# master_jorge3newIMU.net
KiCad netlist of a schematic drawn in EAGLE
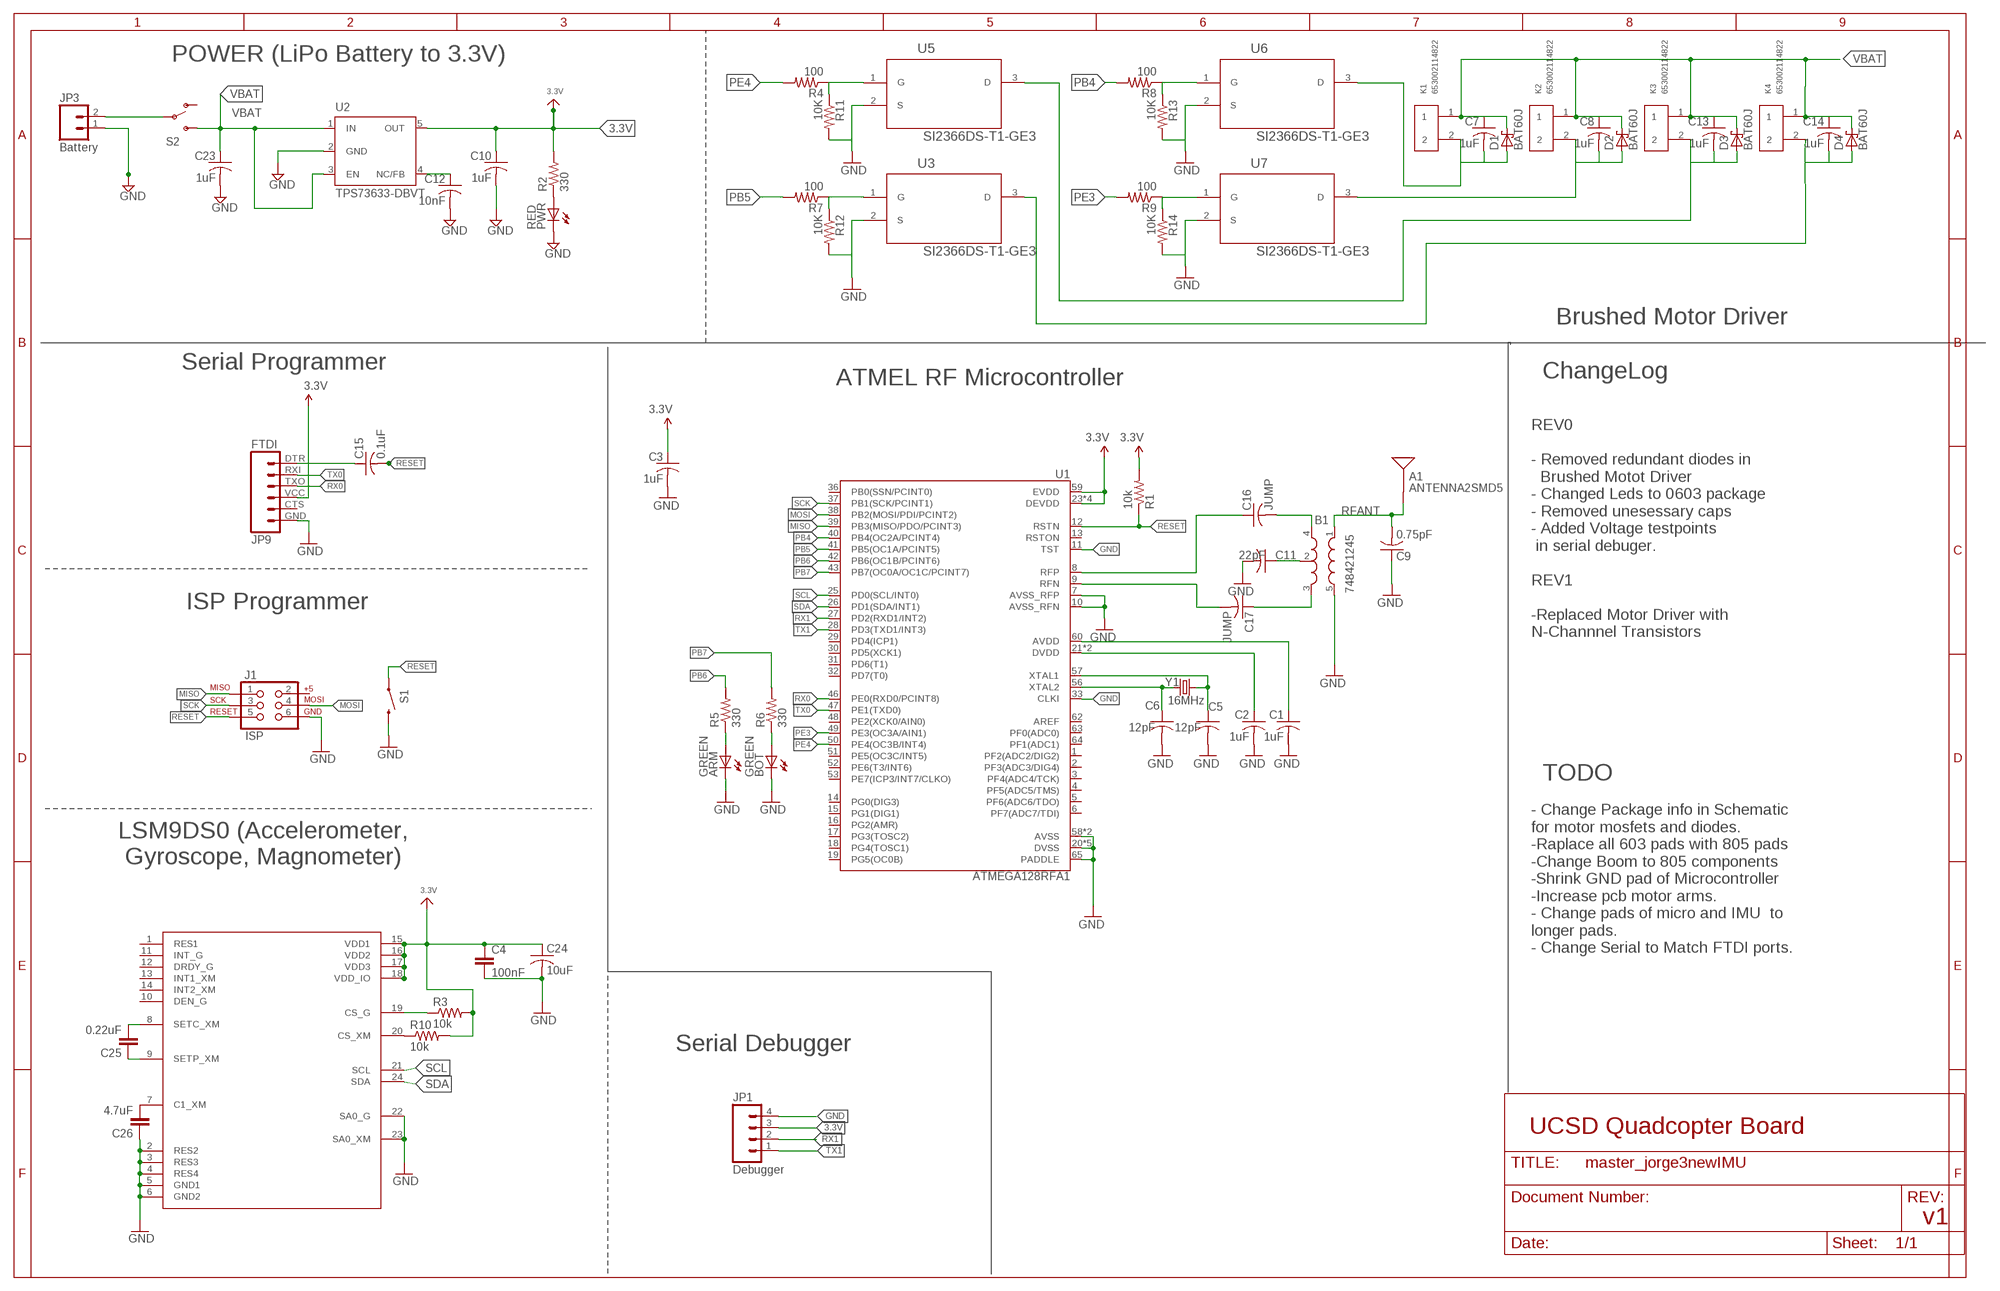
[diagram p0: schematic, sheet 1]

(export (version "E")
  (design (tool "Eeschema 10.0.6"))
  (components
    (comp (ref "A1")
      (value "ANTENNA2SMD5")
      (footprint "eagle-import:ANTENNA-CHIP5")
      (libsource (lib "eagle-import") (part "ANTENNA2SMD5"))
    )
    (comp (ref "ARM")
      (value "GREEN")
      (footprint "eagle-import:CHIP-LED0805")
      (libsource (lib "eagle-import") (part "LEDCHIP-LED0805"))
    )
    (comp (ref "B1")
      (value "748421245")
      (footprint "eagle-import:BALUN")
      (libsource (lib "eagle-import") (part "BALUN0805"))
    )
    (comp (ref "BOT")
      (value "GREEN")
      (footprint "eagle-import:CHIP-LED0805")
      (libsource (lib "eagle-import") (part "LEDCHIP-LED0805"))
    )
    (comp (ref "C1")
      (value "1uF")
      (footprint "eagle-import:C0805")
      (libsource (lib "eagle-import") (part "resistor_C-USC0805"))
    )
    (comp (ref "C2")
      (value "1uF")
      (footprint "eagle-import:C0805")
      (libsource (lib "eagle-import") (part "resistor_C-USC0805"))
    )
    (comp (ref "C3")
      (value "1uF")
      (footprint "eagle-import:C0805")
      (libsource (lib "eagle-import") (part "resistor_C-USC0805"))
    )
    (comp (ref "C4")
      (value "100nF")
      (footprint "eagle-import:0805")
      (libsource (lib "eagle-import") (part "CAP0805"))
    )
    (comp (ref "C5")
      (value "12pF")
      (footprint "eagle-import:C0805")
      (libsource (lib "eagle-import") (part "resistor_C-USC0805"))
    )
    (comp (ref "C6")
      (value "12pF")
      (footprint "eagle-import:C0805")
      (libsource (lib "eagle-import") (part "resistor_C-USC0805"))
    )
    (comp (ref "C7")
      (value "1uF")
      (footprint "eagle-import:C0805")
      (libsource (lib "eagle-import") (part "resistor_C-USC0805"))
    )
    (comp (ref "C8")
      (value "1uF")
      (footprint "eagle-import:C0805")
      (libsource (lib "eagle-import") (part "resistor_C-USC0805"))
    )
    (comp (ref "C9")
      (value "0.75pF")
      (footprint "eagle-import:C0805")
      (libsource (lib "eagle-import") (part "resistor_C-USC0805"))
    )
    (comp (ref "C10")
      (value "1uF")
      (footprint "eagle-import:C0805")
      (libsource (lib "eagle-import") (part "resistor_C-USC0805"))
    )
    (comp (ref "C11")
      (value "22pF")
      (footprint "eagle-import:C0805")
      (libsource (lib "eagle-import") (part "resistor_C-USC0805"))
    )
    (comp (ref "C12")
      (value "10nF")
      (footprint "eagle-import:C0805")
      (libsource (lib "eagle-import") (part "resistor_C-USC0805"))
    )
    (comp (ref "C13")
      (value "1uF")
      (footprint "eagle-import:C0805")
      (libsource (lib "eagle-import") (part "resistor_C-USC0805"))
    )
    (comp (ref "C14")
      (value "1uF")
      (footprint "eagle-import:C0805")
      (libsource (lib "eagle-import") (part "resistor_C-USC0805"))
    )
    (comp (ref "C15")
      (value "0.1uF")
      (footprint "eagle-import:C0805")
      (libsource (lib "eagle-import") (part "resistor_C-USC0805"))
    )
    (comp (ref "C16")
      (value "JUMP")
      (footprint "eagle-import:C0805")
      (libsource (lib "eagle-import") (part "resistor_C-USC0805"))
    )
    (comp (ref "C17")
      (value "JUMP")
      (footprint "eagle-import:C0805")
      (libsource (lib "eagle-import") (part "resistor_C-USC0805"))
    )
    (comp (ref "C23")
      (value "1uF")
      (footprint "eagle-import:C0805")
      (libsource (lib "eagle-import") (part "resistor_C-USC0805"))
    )
    (comp (ref "C24")
      (value "10uF")
      (footprint "eagle-import:C0805")
      (libsource (lib "eagle-import") (part "C-USC0805"))
    )
    (comp (ref "C25")
      (value "0.22uF")
      (footprint "eagle-import:0805")
      (libsource (lib "eagle-import") (part "CAP0805"))
    )
    (comp (ref "C26")
      (value "4.7uF")
      (footprint "eagle-import:0805")
      (libsource (lib "eagle-import") (part "CAP0805"))
    )
    (comp (ref "D1")
      (value "BAT60J")
      (footprint "eagle-import:SOD323_ST")
      (libsource (lib "eagle-import") (part "BAT60J"))
    )
    (comp (ref "D2")
      (value "BAT60J")
      (footprint "eagle-import:SOD323_ST")
      (libsource (lib "eagle-import") (part "BAT60J"))
    )
    (comp (ref "D3")
      (value "BAT60J")
      (footprint "eagle-import:SOD323_ST")
      (libsource (lib "eagle-import") (part "BAT60J"))
    )
    (comp (ref "D4")
      (value "BAT60J")
      (footprint "eagle-import:SOD323_ST")
      (libsource (lib "eagle-import") (part "BAT60J"))
    )
    (comp (ref "J1")
      (value "ISP")
      (footprint "eagle-import:2X3-NS")
      (libsource (lib "eagle-import") (part "AVR_SPI_PRG_6NS"))
    )
    (comp (ref "JP1")
      (value "Debugger")
      (footprint "eagle-import:1X04")
      (libsource (lib "eagle-import") (part "M04PTH"))
    )
    (comp (ref "JP3")
      (value "Battery")
      (footprint "eagle-import:1X02")
      (libsource (lib "eagle-import") (part "M02PTH"))
    )
    (comp (ref "JP9")
      (value "FTDI")
      (footprint "eagle-import:FTDI_BASIC")
      (libsource (lib "eagle-import") (part "FTDI_BASICPTH"))
    )
    (comp (ref "K1")
      (value "653002114822")
      (footprint "eagle-import:653002114822")
      (libsource (lib "eagle-import") (part "653002114822"))
    )
    (comp (ref "K2")
      (value "653002114822")
      (footprint "eagle-import:653002114822")
      (libsource (lib "eagle-import") (part "653002114822"))
    )
    (comp (ref "K3")
      (value "653002114822")
      (footprint "eagle-import:653002114822")
      (libsource (lib "eagle-import") (part "653002114822"))
    )
    (comp (ref "K4")
      (value "653002114822")
      (footprint "eagle-import:653002114822")
      (libsource (lib "eagle-import") (part "653002114822"))
    )
    (comp (ref "PWR")
      (value "RED")
      (footprint "eagle-import:CHIP-LED0805")
      (libsource (lib "eagle-import") (part "LEDCHIP-LED0805"))
    )
    (comp (ref "R1")
      (value "10k")
      (footprint "eagle-import:R0805")
      (libsource (lib "eagle-import") (part "R-US_R0805"))
    )
    (comp (ref "R2")
      (value "330")
      (footprint "eagle-import:R0805")
      (libsource (lib "eagle-import") (part "R-US_R0805"))
    )
    (comp (ref "R3")
      (value "10k")
      (footprint "eagle-import:0805")
      (libsource (lib "eagle-import") (part "RESISTOR0805-RES"))
    )
    (comp (ref "R4")
      (value "100")
      (footprint "eagle-import:R0805")
      (libsource (lib "eagle-import") (part "R-US_R0805"))
    )
    (comp (ref "R5")
      (value "330")
      (footprint "eagle-import:R0805")
      (libsource (lib "eagle-import") (part "R-US_R0805"))
    )
    (comp (ref "R6")
      (value "330")
      (footprint "eagle-import:R0805")
      (libsource (lib "eagle-import") (part "R-US_R0805"))
    )
    (comp (ref "R7")
      (value "100")
      (footprint "eagle-import:R0805")
      (libsource (lib "eagle-import") (part "R-US_R0805"))
    )
    (comp (ref "R8")
      (value "100")
      (footprint "eagle-import:R0805")
      (libsource (lib "eagle-import") (part "R-US_R0805"))
    )
    (comp (ref "R9")
      (value "100")
      (footprint "eagle-import:R0805")
      (libsource (lib "eagle-import") (part "R-US_R0805"))
    )
    (comp (ref "R10")
      (value "10k")
      (footprint "eagle-import:0805")
      (libsource (lib "eagle-import") (part "RESISTOR0805-RES"))
    )
    (comp (ref "R11")
      (value "10K")
      (footprint "eagle-import:R0805")
      (libsource (lib "eagle-import") (part "R-US_R0805"))
    )
    (comp (ref "R12")
      (value "10K")
      (footprint "eagle-import:R0805")
      (libsource (lib "eagle-import") (part "R-US_R0805"))
    )
    (comp (ref "R13")
      (value "10K")
      (footprint "eagle-import:R0805")
      (libsource (lib "eagle-import") (part "R-US_R0805"))
    )
    (comp (ref "R14")
      (value "10K")
      (footprint "eagle-import:R0805")
      (libsource (lib "eagle-import") (part "R-US_R0805"))
    )
    (comp (ref "S1")
      (value "SWITCH-MOMENTARY-2SMD")
      (footprint "eagle-import:TACTILE_SWITCH_SMD")
      (libsource (lib "eagle-import") (part "SWITCH-MOMENTARY-2SMD"))
    )
    (comp (ref "S2")
      (value "SWITCH-SPDTPTH")
      (footprint "eagle-import:SWITCH-SPDT")
      (libsource (lib "eagle-import") (part "SWITCH-SPDTPTH"))
    )
    (comp (ref "U1")
      (value "ATMEGA128RFA1")
      (footprint "eagle-import:QFN-64")
      (libsource (lib "eagle-import") (part "ATMEGA128RFA1"))
    )
    (comp (ref "U2")
      (value "TPS73633-DBVT")
      (footprint "eagle-import:SOT23-DBV")
      (libsource (lib "eagle-import") (part "TPS73633-DBVT"))
    )
    (comp (ref "U3")
      (value "SI2366DS-T1-GE3")
      (footprint "eagle-import:SOT95P237X112-3N")
      (libsource (lib "eagle-import") (part "SI2366DS-T1-GE3"))
    )
    (comp (ref "U4")
      (value "LSM9DS0")
      (footprint "eagle-import:LGA-24")
      (libsource (lib "eagle-import") (part "LSM9DS0"))
    )
    (comp (ref "U5")
      (value "SI2366DS-T1-GE3")
      (footprint "eagle-import:SOT95P237X112-3N")
      (libsource (lib "eagle-import") (part "SI2366DS-T1-GE3"))
    )
    (comp (ref "U6")
      (value "SI2366DS-T1-GE3")
      (footprint "eagle-import:SOT95P237X112-3N")
      (libsource (lib "eagle-import") (part "SI2366DS-T1-GE3"))
    )
    (comp (ref "U7")
      (value "SI2366DS-T1-GE3")
      (footprint "eagle-import:SOT95P237X112-3N")
      (libsource (lib "eagle-import") (part "SI2366DS-T1-GE3"))
    )
    (comp (ref "Y1")
      (value "16MHz")
      (footprint "eagle-import:CRYSTAL-SMD-5X3")
      (libsource (lib "eagle-import") (part "CRYSTAL5X3"))
    )
  )
  (nets
    (net (code "1") (name "/RFANT") (class "Default")
      (node (ref "A1") (pin "FEED") (pinfunction "SIGNAL_FEED") (pintype "bidirectional"))
      (node (ref "B1") (pin "1") (pinfunction "IN_1") (pintype "bidirectional"))
      (node (ref "C9") (pin "2") (pinfunction "2_2") (pintype "passive"))
    )
    (net (code "2") (name "3.3V") (class "Default")
      (node (ref "C10") (pin "1") (pinfunction "1_1") (pintype "passive"))
      (node (ref "C24") (pin "1") (pinfunction "1_1") (pintype "passive"))
      (node (ref "C3") (pin "1") (pinfunction "1_1") (pintype "passive"))
      (node (ref "C4") (pin "1") (pinfunction "1_1") (pintype "passive"))
      (node (ref "JP1") (pin "3") (pinfunction "3_3") (pintype "passive"))
      (node (ref "JP9") (pin "VCC") (pinfunction "4_VCC") (pintype "passive"))
      (node (ref "R1") (pin "2") (pinfunction "2_2") (pintype "passive"))
      (node (ref "R10") (pin "2") (pinfunction "2_2") (pintype "passive"))
      (node (ref "R2") (pin "2") (pinfunction "2_2") (pintype "passive"))
      (node (ref "R3") (pin "2") (pinfunction "2_2") (pintype "passive"))
      (node (ref "U1") (pin "23") (pinfunction "DEVDD_23") (pintype "bidirectional"))
      (node (ref "U1") (pin "34") (pinfunction "DEVDD_34") (pintype "bidirectional"))
      (node (ref "U1") (pin "44") (pinfunction "DEVDD_44") (pintype "bidirectional"))
      (node (ref "U1") (pin "54") (pinfunction "DEVDD_54") (pintype "bidirectional"))
      (node (ref "U1") (pin "59") (pinfunction "EVDD_59") (pintype "bidirectional"))
      (node (ref "U2") (pin "5") (pinfunction "OUT_5") (pintype "passive"))
      (node (ref "U4") (pin "15") (pinfunction "VDD1_15") (pintype "bidirectional"))
      (node (ref "U4") (pin "16") (pinfunction "VDD2_16") (pintype "bidirectional"))
      (node (ref "U4") (pin "17") (pinfunction "VDD3_17") (pintype "bidirectional"))
      (node (ref "U4") (pin "18") (pinfunction "VDD_IO_18") (pintype "bidirectional"))
    )
    (net (code "3") (name "GND") (class "Default")
      (node (ref "ARM") (pin "C") (pinfunction "C_C") (pintype "passive"))
      (node (ref "B1") (pin "5") (pinfunction "GND_5") (pintype "bidirectional"))
      (node (ref "BOT") (pin "C") (pinfunction "C_C") (pintype "passive"))
      (node (ref "C1") (pin "2") (pinfunction "2_2") (pintype "passive"))
      (node (ref "C10") (pin "2") (pinfunction "2_2") (pintype "passive"))
      (node (ref "C11") (pin "2") (pinfunction "2_2") (pintype "passive"))
      (node (ref "C12") (pin "2") (pinfunction "2_2") (pintype "passive"))
      (node (ref "C2") (pin "2") (pinfunction "2_2") (pintype "passive"))
      (node (ref "C23") (pin "2") (pinfunction "2_2") (pintype "passive"))
      (node (ref "C24") (pin "2") (pinfunction "2_2") (pintype "passive"))
      (node (ref "C26") (pin "1") (pinfunction "1_1") (pintype "passive"))
      (node (ref "C3") (pin "2") (pinfunction "2_2") (pintype "passive"))
      (node (ref "C4") (pin "2") (pinfunction "2_2") (pintype "passive"))
      (node (ref "C5") (pin "2") (pinfunction "2_2") (pintype "passive"))
      (node (ref "C6") (pin "2") (pinfunction "2_2") (pintype "passive"))
      (node (ref "C9") (pin "1") (pinfunction "1_1") (pintype "passive"))
      (node (ref "J1") (pin "6") (pinfunction "6_6") (pintype "passive"))
      (node (ref "JP1") (pin "4") (pinfunction "4_4") (pintype "passive"))
      (node (ref "JP3") (pin "1") (pinfunction "1_1") (pintype "passive"))
      (node (ref "JP9") (pin "GND") (pinfunction "6_GND") (pintype "passive"))
      (node (ref "PWR") (pin "C") (pinfunction "C_C") (pintype "passive"))
      (node (ref "R11") (pin "2") (pinfunction "2_2") (pintype "passive"))
      (node (ref "R12") (pin "2") (pinfunction "2_2") (pintype "passive"))
      (node (ref "R13") (pin "2") (pinfunction "2_2") (pintype "passive"))
      (node (ref "R14") (pin "2") (pinfunction "2_2") (pintype "passive"))
      (node (ref "S1") (pin "3") (pinfunction "2_3") (pintype "passive"))
      (node (ref "U1") (pin "10") (pinfunction "AVSS_RFN_10") (pintype "bidirectional"))
      (node (ref "U1") (pin "11") (pinfunction "TST_11") (pintype "bidirectional"))
      (node (ref "U1") (pin "20") (pinfunction "DVSS_20") (pintype "bidirectional"))
      (node (ref "U1") (pin "24") (pinfunction "DVSS_24") (pintype "bidirectional"))
      (node (ref "U1") (pin "33") (pinfunction "CLKI_33") (pintype "bidirectional"))
      (node (ref "U1") (pin "35") (pinfunction "DVSS_35") (pintype "bidirectional"))
      (node (ref "U1") (pin "45") (pinfunction "DVSS_45") (pintype "bidirectional"))
      (node (ref "U1") (pin "55") (pinfunction "DVSS_55") (pintype "bidirectional"))
      (node (ref "U1") (pin "58") (pinfunction "AVSS_58") (pintype "bidirectional"))
      (node (ref "U1") (pin "61") (pinfunction "AVSS_61") (pintype "bidirectional"))
      (node (ref "U1") (pin "65") (pinfunction "PADDLE_65") (pintype "bidirectional"))
      (node (ref "U1") (pin "7") (pinfunction "AVSS_RFP_7") (pintype "bidirectional"))
      (node (ref "U2") (pin "2") (pinfunction "GND_2") (pintype "input"))
      (node (ref "U3") (pin "2") (pinfunction "S_2") (pintype "passive"))
      (node (ref "U4") (pin "2") (pinfunction "RES2_2") (pintype "bidirectional"))
      (node (ref "U4") (pin "22") (pinfunction "SA0_G_22") (pintype "bidirectional"))
      (node (ref "U4") (pin "23") (pinfunction "SA0_XM_23") (pintype "bidirectional"))
      (node (ref "U4") (pin "3") (pinfunction "RES3_3") (pintype "bidirectional"))
      (node (ref "U4") (pin "4") (pinfunction "RES4_4") (pintype "bidirectional"))
      (node (ref "U4") (pin "5") (pinfunction "GND1_5") (pintype "bidirectional"))
      (node (ref "U4") (pin "6") (pinfunction "GND2_6") (pintype "bidirectional"))
      (node (ref "U5") (pin "2") (pinfunction "S_2") (pintype "passive"))
      (node (ref "U6") (pin "2") (pinfunction "S_2") (pintype "passive"))
      (node (ref "U7") (pin "2") (pinfunction "S_2") (pintype "passive"))
    )
    (net (code "4") (name "MISO") (class "Default")
      (node (ref "J1") (pin "1") (pinfunction "1_1") (pintype "passive"))
      (node (ref "U1") (pin "39") (pinfunction "PB3(MISO/PDO/PCINT3)_39") (pintype "bidirectional"))
    )
    (net (code "5") (name "MOSI") (class "Default")
      (node (ref "J1") (pin "4") (pinfunction "4_4") (pintype "passive"))
      (node (ref "U1") (pin "38") (pinfunction "PB2(MOSI/PDI/PCINT2)_38") (pintype "bidirectional"))
    )
    (net (code "6") (name "Net-(ARM-PadA)") (class "Default")
      (node (ref "ARM") (pin "A") (pinfunction "A_A") (pintype "passive"))
      (node (ref "R5") (pin "1") (pinfunction "1_1") (pintype "passive"))
    )
    (net (code "7") (name "Net-(B1-GND-Pad2)") (class "Default")
      (node (ref "B1") (pin "2") (pinfunction "GND_2") (pintype "bidirectional"))
      (node (ref "C11") (pin "1") (pinfunction "1_1") (pintype "passive"))
    )
    (net (code "8") (name "Net-(B1-OUT1)") (class "Default")
      (node (ref "B1") (pin "4") (pinfunction "OUT1_4") (pintype "bidirectional"))
      (node (ref "C16") (pin "2") (pinfunction "2_2") (pintype "passive"))
    )
    (net (code "9") (name "Net-(B1-OUT2)") (class "Default")
      (node (ref "B1") (pin "3") (pinfunction "OUT2_3") (pintype "bidirectional"))
      (node (ref "C17") (pin "1") (pinfunction "1_1") (pintype "passive"))
    )
    (net (code "10") (name "Net-(BOT-PadA)") (class "Default")
      (node (ref "BOT") (pin "A") (pinfunction "A_A") (pintype "passive"))
      (node (ref "R6") (pin "1") (pinfunction "1_1") (pintype "passive"))
    )
    (net (code "11") (name "Net-(C2-Pad1)") (class "Default")
      (node (ref "C2") (pin "1") (pinfunction "1_1") (pintype "passive"))
      (node (ref "U1") (pin "21") (pinfunction "DVDD_21") (pintype "bidirectional"))
      (node (ref "U1") (pin "22") (pinfunction "DVDD_22") (pintype "bidirectional"))
    )
    (net (code "12") (name "Net-(C7-Pad2)") (class "Default")
      (node (ref "C7") (pin "2") (pinfunction "2_2") (pintype "passive"))
      (node (ref "D1") (pin "A") (pinfunction "A_A") (pintype "passive"))
    )
    (net (code "13") (name "Net-(C13-Pad2)") (class "Default")
      (node (ref "C13") (pin "2") (pinfunction "2_2") (pintype "passive"))
      (node (ref "D3") (pin "A") (pinfunction "A_A") (pintype "passive"))
    )
    (net (code "14") (name "Net-(C14-Pad2)") (class "Default")
      (node (ref "C14") (pin "2") (pinfunction "2_2") (pintype "passive"))
      (node (ref "D4") (pin "A") (pinfunction "A_A") (pintype "passive"))
    )
    (net (code "15") (name "Net-(JP9-1)") (class "Default")
      (node (ref "C15") (pin "1") (pinfunction "1_1") (pintype "passive"))
      (node (ref "JP9") (pin "DTR") (pinfunction "1_DTR") (pintype "passive"))
    )
    (net (code "16") (name "Net-(PWR-PadA)") (class "Default")
      (node (ref "PWR") (pin "A") (pinfunction "A_A") (pintype "passive"))
      (node (ref "R2") (pin "1") (pinfunction "1_1") (pintype "passive"))
    )
    (net (code "17") (name "Net-(S2-P)") (class "Default")
      (node (ref "JP3") (pin "2") (pinfunction "2_2") (pintype "passive"))
      (node (ref "S2") (pin "2") (pinfunction "P_2") (pintype "passive"))
    )
    (net (code "18") (name "Net-(U1-AVDD)") (class "Default")
      (node (ref "C1") (pin "1") (pinfunction "1_1") (pintype "passive"))
      (node (ref "U1") (pin "60") (pinfunction "AVDD_60") (pintype "bidirectional"))
    )
    (net (code "19") (name "Net-(U1-RFN)") (class "Default")
      (node (ref "C17") (pin "2") (pinfunction "2_2") (pintype "passive"))
      (node (ref "U1") (pin "9") (pinfunction "RFN_9") (pintype "bidirectional"))
    )
    (net (code "20") (name "Net-(U1-RFP)") (class "Default")
      (node (ref "C16") (pin "1") (pinfunction "1_1") (pintype "passive"))
      (node (ref "U1") (pin "8") (pinfunction "RFP_8") (pintype "bidirectional"))
    )
    (net (code "21") (name "Net-(U1-XTAL1)") (class "Default")
      (node (ref "C5") (pin "1") (pinfunction "1_1") (pintype "passive"))
      (node (ref "U1") (pin "57") (pinfunction "XTAL1_57") (pintype "bidirectional"))
      (node (ref "Y1") (pin "3") (pinfunction "2_3") (pintype "passive"))
    )
    (net (code "22") (name "Net-(U1-XTAL2)") (class "Default")
      (node (ref "C6") (pin "1") (pinfunction "1_1") (pintype "passive"))
      (node (ref "U1") (pin "56") (pinfunction "XTAL2_56") (pintype "bidirectional"))
      (node (ref "Y1") (pin "1") (pinfunction "1_1") (pintype "passive"))
    )
    (net (code "23") (name "Net-(U2-NC{slash}FB)") (class "Default")
      (node (ref "C12") (pin "1") (pinfunction "1_1") (pintype "passive"))
      (node (ref "U2") (pin "4") (pinfunction "NC/FB_4") (pintype "passive"))
    )
    (net (code "24") (name "Net-(U3-D)") (class "Default")
      (node (ref "K4") (pin "2") (pinfunction "2_2") (pintype "bidirectional"))
      (node (ref "U3") (pin "3") (pinfunction "D_3") (pintype "passive"))
    )
    (net (code "25") (name "Net-(U3-G)") (class "Default")
      (node (ref "R12") (pin "1") (pinfunction "1_1") (pintype "passive"))
      (node (ref "R7") (pin "1") (pinfunction "1_1") (pintype "passive"))
      (node (ref "U3") (pin "1") (pinfunction "G_1") (pintype "passive"))
    )
    (net (code "26") (name "Net-(U4-C1_XM)") (class "Default")
      (node (ref "C26") (pin "2") (pinfunction "2_2") (pintype "passive"))
      (node (ref "U4") (pin "7") (pinfunction "C1_XM_7") (pintype "bidirectional"))
    )
    (net (code "27") (name "Net-(U4-CS_G)") (class "Default")
      (node (ref "R3") (pin "1") (pinfunction "1_1") (pintype "passive"))
      (node (ref "U4") (pin "19") (pinfunction "CS_G_19") (pintype "bidirectional"))
    )
    (net (code "28") (name "Net-(U4-CS_XM)") (class "Default")
      (node (ref "R10") (pin "1") (pinfunction "1_1") (pintype "passive"))
      (node (ref "U4") (pin "20") (pinfunction "CS_XM_20") (pintype "bidirectional"))
    )
    (net (code "29") (name "Net-(U4-SETC_XM)") (class "Default")
      (node (ref "C25") (pin "2") (pinfunction "2_2") (pintype "passive"))
      (node (ref "U4") (pin "8") (pinfunction "SETC_XM_8") (pintype "bidirectional"))
    )
    (net (code "30") (name "Net-(U4-SETP_XM)") (class "Default")
      (node (ref "C25") (pin "1") (pinfunction "1_1") (pintype "passive"))
      (node (ref "U4") (pin "9") (pinfunction "SETP_XM_9") (pintype "bidirectional"))
    )
    (net (code "31") (name "Net-(U5-D)") (class "Default")
      (node (ref "K3") (pin "2") (pinfunction "2_2") (pintype "bidirectional"))
      (node (ref "U5") (pin "3") (pinfunction "D_3") (pintype "passive"))
    )
    (net (code "32") (name "Net-(U5-G)") (class "Default")
      (node (ref "R11") (pin "1") (pinfunction "1_1") (pintype "passive"))
      (node (ref "R4") (pin "1") (pinfunction "1_1") (pintype "passive"))
      (node (ref "U5") (pin "1") (pinfunction "G_1") (pintype "passive"))
    )
    (net (code "33") (name "Net-(U6-D)") (class "Default")
      (node (ref "K1") (pin "2") (pinfunction "2_2") (pintype "bidirectional"))
      (node (ref "U6") (pin "3") (pinfunction "D_3") (pintype "passive"))
    )
    (net (code "34") (name "Net-(U6-G)") (class "Default")
      (node (ref "R13") (pin "1") (pinfunction "1_1") (pintype "passive"))
      (node (ref "R8") (pin "1") (pinfunction "1_1") (pintype "passive"))
      (node (ref "U6") (pin "1") (pinfunction "G_1") (pintype "passive"))
    )
    (net (code "35") (name "Net-(U7-D)") (class "Default")
      (node (ref "C8") (pin "2") (pinfunction "2_2") (pintype "passive"))
      (node (ref "D2") (pin "A") (pinfunction "A_A") (pintype "passive"))
      (node (ref "K2") (pin "2") (pinfunction "2_2") (pintype "bidirectional"))
      (node (ref "U7") (pin "3") (pinfunction "D_3") (pintype "passive"))
    )
    (net (code "36") (name "Net-(U7-G)") (class "Default")
      (node (ref "R14") (pin "1") (pinfunction "1_1") (pintype "passive"))
      (node (ref "R9") (pin "1") (pinfunction "1_1") (pintype "passive"))
      (node (ref "U7") (pin "1") (pinfunction "G_1") (pintype "passive"))
    )
    (net (code "37") (name "PB4") (class "Default")
      (node (ref "R8") (pin "2") (pinfunction "2_2") (pintype "passive"))
      (node (ref "U1") (pin "40") (pinfunction "PB4(OC2A/PCINT4)_40") (pintype "bidirectional"))
    )
    (net (code "38") (name "PB5") (class "Default")
      (node (ref "R7") (pin "2") (pinfunction "2_2") (pintype "passive"))
      (node (ref "U1") (pin "41") (pinfunction "PB5(OC1A/PCINT5)_41") (pintype "bidirectional"))
    )
    (net (code "39") (name "PB6") (class "Default")
      (node (ref "R5") (pin "2") (pinfunction "2_2") (pintype "passive"))
      (node (ref "U1") (pin "42") (pinfunction "PB6(OC1B/PCINT6)_42") (pintype "bidirectional"))
    )
    (net (code "40") (name "PB7") (class "Default")
      (node (ref "R6") (pin "2") (pinfunction "2_2") (pintype "passive"))
      (node (ref "U1") (pin "43") (pinfunction "PB7(OC0A/OC1C/PCINT7)_43") (pintype "bidirectional"))
    )
    (net (code "41") (name "PE3") (class "Default")
      (node (ref "R9") (pin "2") (pinfunction "2_2") (pintype "passive"))
      (node (ref "U1") (pin "49") (pinfunction "PE3(OC3A/AIN1)_49") (pintype "bidirectional"))
    )
    (net (code "42") (name "PE4") (class "Default")
      (node (ref "R4") (pin "2") (pinfunction "2_2") (pintype "passive"))
      (node (ref "U1") (pin "50") (pinfunction "PE4(OC3B/INT4)_50") (pintype "bidirectional"))
    )
    (net (code "43") (name "RESET") (class "Default")
      (node (ref "C15") (pin "2") (pinfunction "2_2") (pintype "passive"))
      (node (ref "J1") (pin "5") (pinfunction "5_5") (pintype "passive"))
      (node (ref "R1") (pin "1") (pinfunction "1_1") (pintype "passive"))
      (node (ref "S1") (pin "1") (pinfunction "1_1") (pintype "passive"))
      (node (ref "U1") (pin "12") (pinfunction "RSTN_12") (pintype "bidirectional"))
    )
    (net (code "44") (name "RX0") (class "Default")
      (node (ref "JP9") (pin "TXO") (pinfunction "3_TXO") (pintype "passive"))
      (node (ref "U1") (pin "46") (pinfunction "PE0(RXD0/PCINT8)_46") (pintype "bidirectional"))
    )
    (net (code "45") (name "RX1") (class "Default")
      (node (ref "JP1") (pin "2") (pinfunction "2_2") (pintype "passive"))
      (node (ref "U1") (pin "27") (pinfunction "PD2(RXD1/INT2)_27") (pintype "bidirectional"))
    )
    (net (code "46") (name "SCK") (class "Default")
      (node (ref "J1") (pin "3") (pinfunction "3_3") (pintype "passive"))
      (node (ref "U1") (pin "37") (pinfunction "PB1(SCK/PCINT1)_37") (pintype "bidirectional"))
    )
    (net (code "47") (name "SCL") (class "Default")
      (node (ref "U1") (pin "25") (pinfunction "PD0(SCL/INT0)_25") (pintype "bidirectional"))
      (node (ref "U4") (pin "21") (pinfunction "SCL_21") (pintype "bidirectional"))
    )
    (net (code "48") (name "SDA") (class "Default")
      (node (ref "U1") (pin "26") (pinfunction "PD1(SDA/INT1)_26") (pintype "bidirectional"))
      (node (ref "U4") (pin "24") (pinfunction "SDA_24") (pintype "bidirectional"))
    )
    (net (code "49") (name "TX0") (class "Default")
      (node (ref "JP9") (pin "RXI") (pinfunction "2_RXI") (pintype "passive"))
      (node (ref "U1") (pin "47") (pinfunction "PE1(TXD0)_47") (pintype "bidirectional"))
    )
    (net (code "50") (name "TX1") (class "Default")
      (node (ref "JP1") (pin "1") (pinfunction "1_1") (pintype "passive"))
      (node (ref "U1") (pin "28") (pinfunction "PD3(TXD1/INT3)_28") (pintype "bidirectional"))
    )
    (net (code "51") (name "VBAT") (class "Default")
      (node (ref "C13") (pin "1") (pinfunction "1_1") (pintype "passive"))
      (node (ref "C14") (pin "1") (pinfunction "1_1") (pintype "passive"))
      (node (ref "C23") (pin "1") (pinfunction "1_1") (pintype "passive"))
      (node (ref "C7") (pin "1") (pinfunction "1_1") (pintype "passive"))
      (node (ref "C8") (pin "1") (pinfunction "1_1") (pintype "passive"))
      (node (ref "D1") (pin "C") (pinfunction "C_C") (pintype "passive"))
      (node (ref "D2") (pin "C") (pinfunction "C_C") (pintype "passive"))
      (node (ref "D3") (pin "C") (pinfunction "C_C") (pintype "passive"))
      (node (ref "D4") (pin "C") (pinfunction "C_C") (pintype "passive"))
      (node (ref "K1") (pin "1") (pinfunction "1_1") (pintype "bidirectional"))
      (node (ref "K2") (pin "1") (pinfunction "1_1") (pintype "bidirectional"))
      (node (ref "K3") (pin "1") (pinfunction "1_1") (pintype "bidirectional"))
      (node (ref "K4") (pin "1") (pinfunction "1_1") (pintype "bidirectional"))
      (node (ref "S2") (pin "3") (pinfunction "S_3") (pintype "passive"))
      (node (ref "U2") (pin "1") (pinfunction "IN_1") (pintype "input"))
      (node (ref "U2") (pin "3") (pinfunction "EN_3") (pintype "power_in"))
    )
    (net (code "52") (name "unconnected-(J1-Pad2)") (class "Default")
      (node (ref "J1") (pin "2") (pinfunction "2_2") (pintype "passive"))
    )
    (net (code "53") (name "unconnected-(JP9-5-PadCTS)") (class "Default")
      (node (ref "JP9") (pin "CTS") (pinfunction "5_CTS") (pintype "passive"))
    )
    (net (code "54") (name "unconnected-(S2-O-Pad1)") (class "Default")
      (node (ref "S2") (pin "1") (pinfunction "O_1") (pintype "passive"))
    )
    (net (code "55") (name "unconnected-(U1-AREF-Pad62)") (class "Default")
      (node (ref "U1") (pin "62") (pinfunction "AREF_62") (pintype "bidirectional"))
    )
    (net (code "56") (name "unconnected-(U1-PB0(SSN{slash}PCINT0)-Pad36)") (class "Default")
      (node (ref "U1") (pin "36") (pinfunction "PB0(SSN/PCINT0)_36") (pintype "bidirectional"))
    )
    (net (code "57") (name "unconnected-(U1-PD4(ICP1)-Pad29)") (class "Default")
      (node (ref "U1") (pin "29") (pinfunction "PD4(ICP1)_29") (pintype "bidirectional"))
    )
    (net (code "58") (name "unconnected-(U1-PD5(XCK1)-Pad30)") (class "Default")
      (node (ref "U1") (pin "30") (pinfunction "PD5(XCK1)_30") (pintype "bidirectional"))
    )
    (net (code "59") (name "unconnected-(U1-PD6(T1)-Pad31)") (class "Default")
      (node (ref "U1") (pin "31") (pinfunction "PD6(T1)_31") (pintype "bidirectional"))
    )
    (net (code "60") (name "unconnected-(U1-PD7(T0)-Pad32)") (class "Default")
      (node (ref "U1") (pin "32") (pinfunction "PD7(T0)_32") (pintype "bidirectional"))
    )
    (net (code "61") (name "unconnected-(U1-PE2(XCK0{slash}AIN0)-Pad48)") (class "Default")
      (node (ref "U1") (pin "48") (pinfunction "PE2(XCK0/AIN0)_48") (pintype "bidirectional"))
    )
    (net (code "62") (name "unconnected-(U1-PE5(OC3C{slash}INT5)-Pad51)") (class "Default")
      (node (ref "U1") (pin "51") (pinfunction "PE5(OC3C/INT5)_51") (pintype "bidirectional"))
    )
    (net (code "63") (name "unconnected-(U1-PE6(T3{slash}INT6)-Pad52)") (class "Default")
      (node (ref "U1") (pin "52") (pinfunction "PE6(T3/INT6)_52") (pintype "bidirectional"))
    )
    (net (code "64") (name "unconnected-(U1-PE7(ICP3{slash}INT7{slash}CLKO)-Pad53)") (class "Default")
      (node (ref "U1") (pin "53") (pinfunction "PE7(ICP3/INT7/CLKO)_53") (pintype "bidirectional"))
    )
    (net (code "65") (name "unconnected-(U1-PF0(ADC0)-Pad63)") (class "Default")
      (node (ref "U1") (pin "63") (pinfunction "PF0(ADC0)_63") (pintype "bidirectional"))
    )
    (net (code "66") (name "unconnected-(U1-PF1(ADC1)-Pad64)") (class "Default")
      (node (ref "U1") (pin "64") (pinfunction "PF1(ADC1)_64") (pintype "bidirectional"))
    )
    (net (code "67") (name "unconnected-(U1-PF2(ADC2{slash}DIG2)-Pad1)") (class "Default")
      (node (ref "U1") (pin "1") (pinfunction "PF2(ADC2/DIG2)_1") (pintype "bidirectional"))
    )
    (net (code "68") (name "unconnected-(U1-PF3(ADC3{slash}DIG4)-Pad2)") (class "Default")
      (node (ref "U1") (pin "2") (pinfunction "PF3(ADC3/DIG4)_2") (pintype "bidirectional"))
    )
    (net (code "69") (name "unconnected-(U1-PF4(ADC4{slash}TCK)-Pad3)") (class "Default")
      (node (ref "U1") (pin "3") (pinfunction "PF4(ADC4/TCK)_3") (pintype "bidirectional"))
    )
    (net (code "70") (name "unconnected-(U1-PF5(ADC5{slash}TMS)-Pad4)") (class "Default")
      (node (ref "U1") (pin "4") (pinfunction "PF5(ADC5/TMS)_4") (pintype "bidirectional"))
    )
    (net (code "71") (name "unconnected-(U1-PF6(ADC6{slash}TDO)-Pad5)") (class "Default")
      (node (ref "U1") (pin "5") (pinfunction "PF6(ADC6/TDO)_5") (pintype "bidirectional"))
    )
    (net (code "72") (name "unconnected-(U1-PF7(ADC7{slash}TDI)-Pad6)") (class "Default")
      (node (ref "U1") (pin "6") (pinfunction "PF7(ADC7/TDI)_6") (pintype "bidirectional"))
    )
    (net (code "73") (name "unconnected-(U1-PG0(DIG3)-Pad14)") (class "Default")
      (node (ref "U1") (pin "14") (pinfunction "PG0(DIG3)_14") (pintype "bidirectional"))
    )
    (net (code "74") (name "unconnected-(U1-PG1(DIG1)-Pad15)") (class "Default")
      (node (ref "U1") (pin "15") (pinfunction "PG1(DIG1)_15") (pintype "bidirectional"))
    )
    (net (code "75") (name "unconnected-(U1-PG2(AMR)-Pad16)") (class "Default")
      (node (ref "U1") (pin "16") (pinfunction "PG2(AMR)_16") (pintype "bidirectional"))
    )
    (net (code "76") (name "unconnected-(U1-PG3(TOSC2)-Pad17)") (class "Default")
      (node (ref "U1") (pin "17") (pinfunction "PG3(TOSC2)_17") (pintype "bidirectional"))
    )
    (net (code "77") (name "unconnected-(U1-PG4(TOSC1)-Pad18)") (class "Default")
      (node (ref "U1") (pin "18") (pinfunction "PG4(TOSC1)_18") (pintype "bidirectional"))
    )
    (net (code "78") (name "unconnected-(U1-PG5(OC0B)-Pad19)") (class "Default")
      (node (ref "U1") (pin "19") (pinfunction "PG5(OC0B)_19") (pintype "bidirectional"))
    )
    (net (code "79") (name "unconnected-(U1-RSTON-Pad13)") (class "Default")
      (node (ref "U1") (pin "13") (pinfunction "RSTON_13") (pintype "bidirectional"))
    )
    (net (code "80") (name "unconnected-(U4-DEN_G-Pad10)") (class "Default")
      (node (ref "U4") (pin "10") (pinfunction "DEN_G_10") (pintype "bidirectional"))
    )
    (net (code "81") (name "unconnected-(U4-DRDY_G-Pad12)") (class "Default")
      (node (ref "U4") (pin "12") (pinfunction "DRDY_G_12") (pintype "bidirectional"))
    )
    (net (code "82") (name "unconnected-(U4-INT1_XM-Pad13)") (class "Default")
      (node (ref "U4") (pin "13") (pinfunction "INT1_XM_13") (pintype "bidirectional"))
    )
    (net (code "83") (name "unconnected-(U4-INT2_XM-Pad14)") (class "Default")
      (node (ref "U4") (pin "14") (pinfunction "INT2_XM_14") (pintype "bidirectional"))
    )
    (net (code "84") (name "unconnected-(U4-INT_G-Pad11)") (class "Default")
      (node (ref "U4") (pin "11") (pinfunction "INT_G_11") (pintype "bidirectional"))
    )
    (net (code "85") (name "unconnected-(U4-RES1-Pad1)") (class "Default")
      (node (ref "U4") (pin "1") (pinfunction "RES1_1") (pintype "bidirectional"))
    )
  )
)
